# USB_PCB.net
KiCad netlist of a schematic drawn in Altium Designer
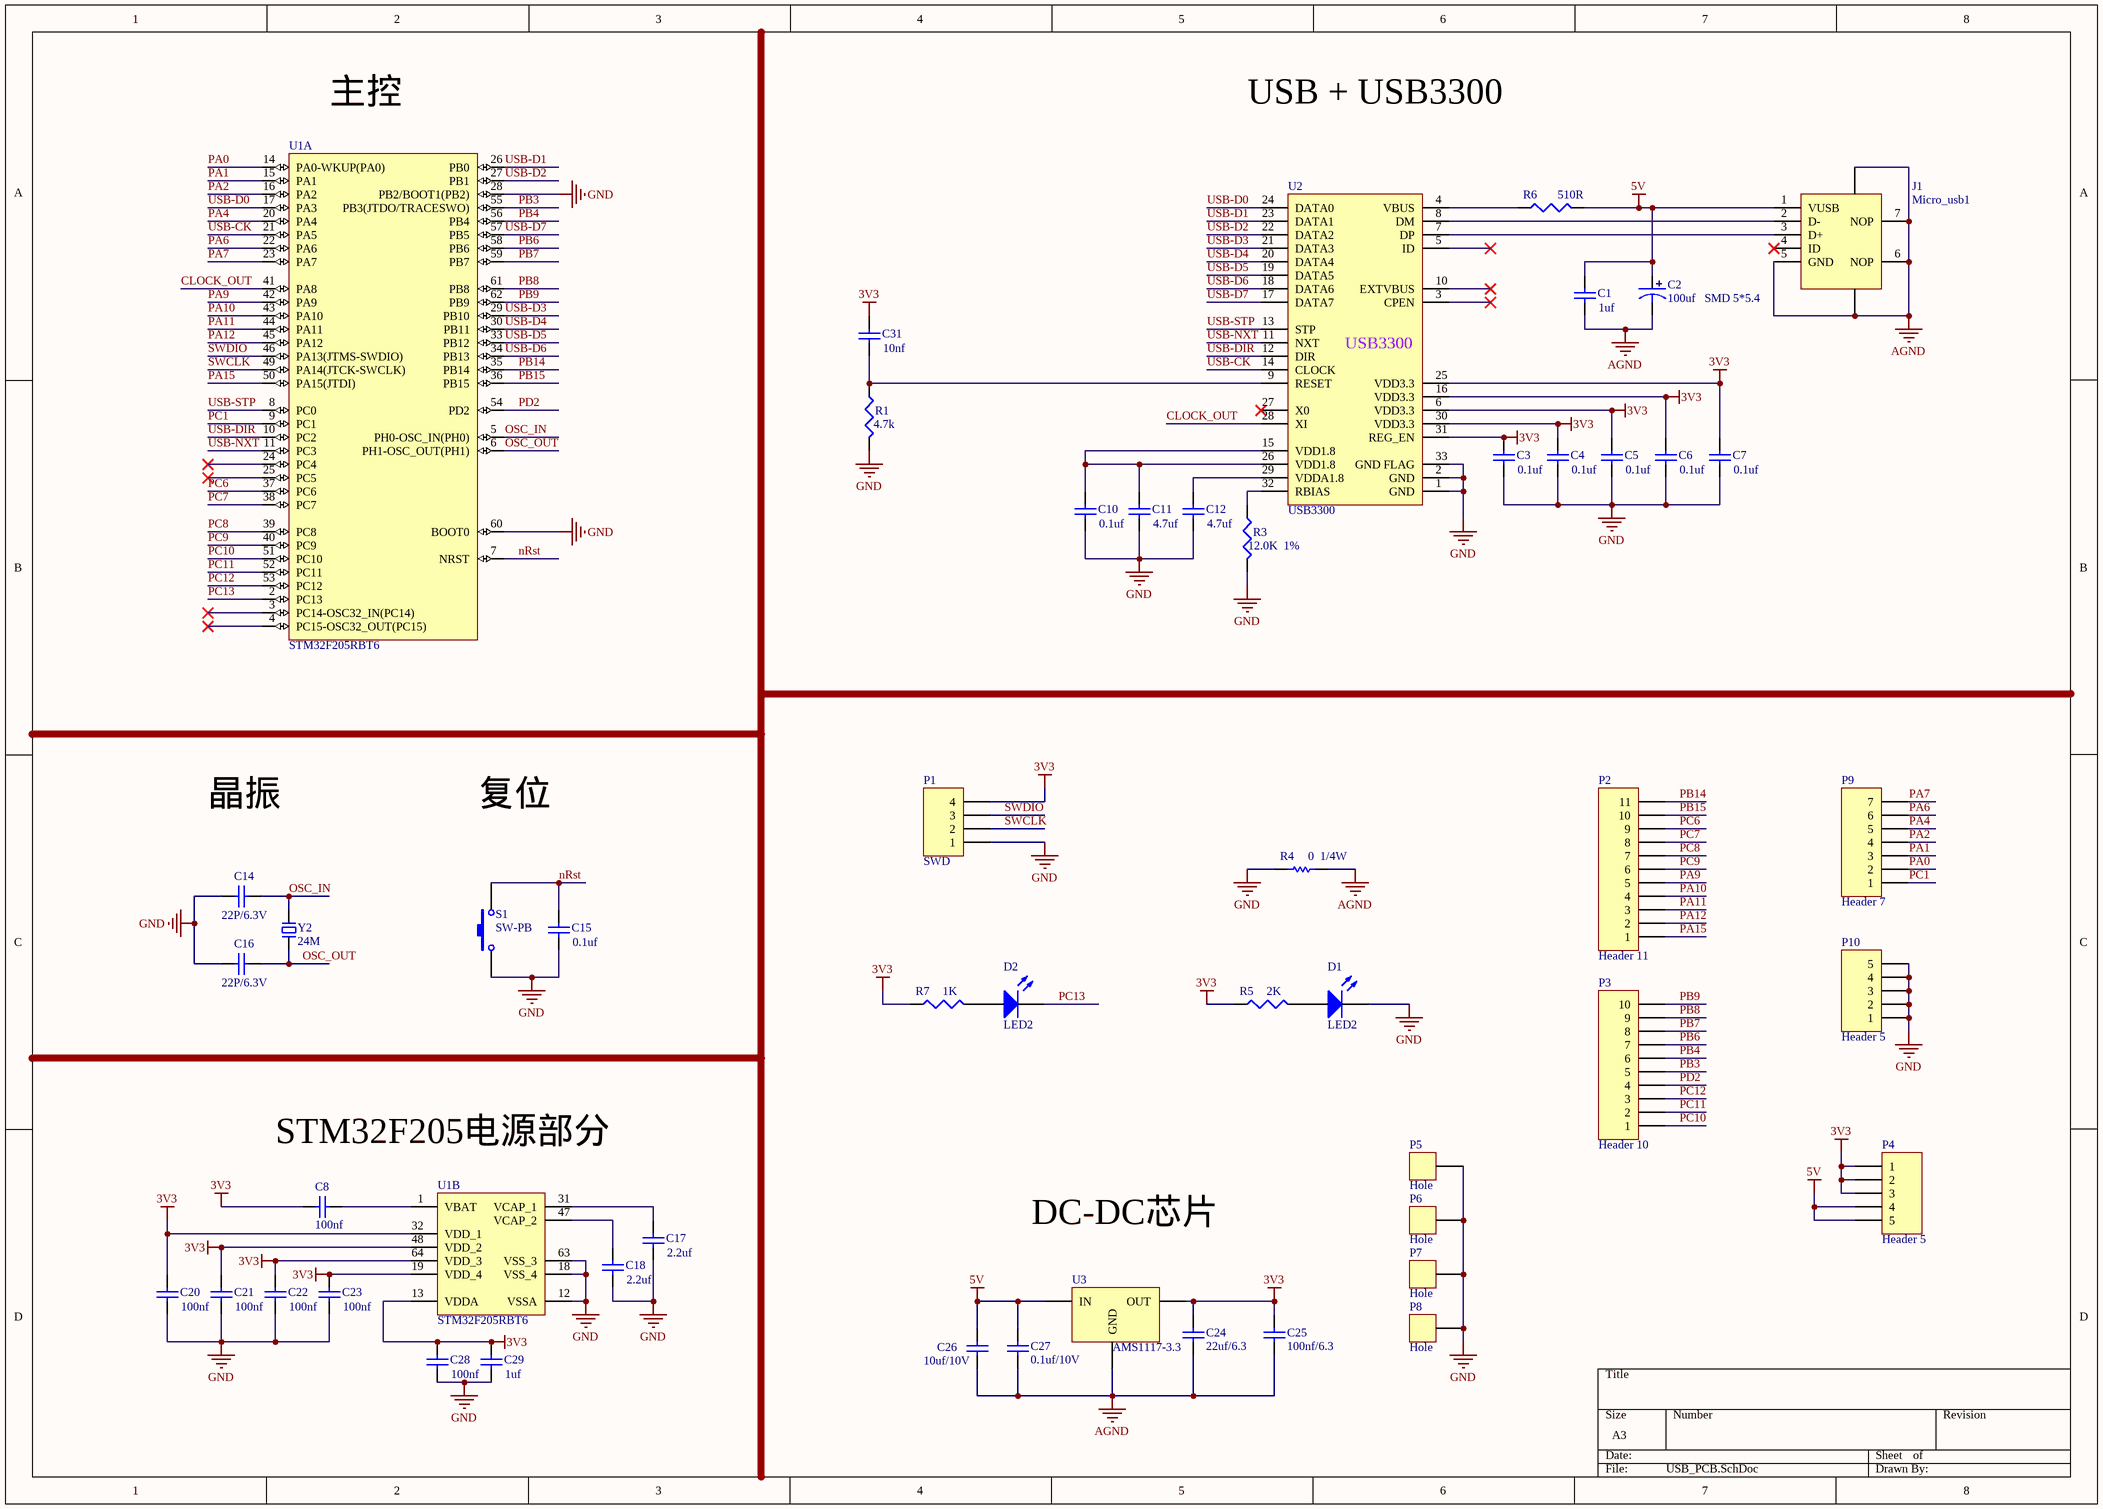
[diagram p0: USB_PCB.SchDoc]

(export (version "E")
  (design (tool "Eeschema 10.0.6"))
  (components
    (comp (ref "C1")
      (value "1uf")
      (footprint "j1-0603")
      (description "Capacitor (Semiconductor SIM Model)")
      (fields (field (name "PUBLISHER") "Altium Limited"))
      (libsource (lib "Miscellaneous Devices") (part "Cap Semi"))
    )
    (comp (ref "C2")
      (value "100uf   SMD 5*5.4")
      (footprint "SMD-EC5.0X5.3X5.4")
      (description "贴片电解电容")
      (libsource (lib "电容") (part "SMD_ECAP"))
    )
    (comp (ref "C3")
      (value "0.1uf")
      (footprint "j1-0603")
      (description "Capacitor (Semiconductor SIM Model)")
      (fields (field (name "PUBLISHER") "Altium Limited"))
      (libsource (lib "Miscellaneous Devices") (part "Cap Semi"))
    )
    (comp (ref "C4")
      (value "0.1uf")
      (footprint "j1-0603")
      (description "Capacitor (Semiconductor SIM Model)")
      (fields (field (name "PUBLISHER") "Altium Limited"))
      (libsource (lib "Miscellaneous Devices") (part "Cap Semi"))
    )
    (comp (ref "C5")
      (value "0.1uf")
      (footprint "j1-0603")
      (description "Capacitor (Semiconductor SIM Model)")
      (fields (field (name "PUBLISHER") "Altium Limited"))
      (libsource (lib "Miscellaneous Devices") (part "Cap Semi"))
    )
    (comp (ref "C6")
      (value "0.1uf")
      (footprint "j1-0603")
      (description "Capacitor (Semiconductor SIM Model)")
      (fields (field (name "PUBLISHER") "Altium Limited"))
      (libsource (lib "Miscellaneous Devices") (part "Cap Semi"))
    )
    (comp (ref "C7")
      (value "0.1uf")
      (footprint "j1-0603")
      (description "Capacitor (Semiconductor SIM Model)")
      (fields (field (name "PUBLISHER") "Altium Limited"))
      (libsource (lib "Miscellaneous Devices") (part "Cap Semi"))
    )
    (comp (ref "C8")
      (value "100nf")
      (footprint "j1-0603")
      (description "Capacitor (Semiconductor SIM Model)")
      (fields (field (name "PUBLISHER") "Altium Limited"))
      (libsource (lib "Miscellaneous Devices") (part "Cap Semi"))
    )
    (comp (ref "C10")
      (value "0.1uf")
      (footprint "j1-0603")
      (description "Capacitor (Semiconductor SIM Model)")
      (fields (field (name "PUBLISHER") "Altium Limited"))
      (libsource (lib "Miscellaneous Devices") (part "Cap Semi"))
    )
    (comp (ref "C11")
      (value "4.7uf")
      (footprint "j1-0603")
      (description "Capacitor (Semiconductor SIM Model)")
      (fields (field (name "PUBLISHER") "Altium Limited"))
      (libsource (lib "Miscellaneous Devices") (part "Cap Semi"))
    )
    (comp (ref "C12")
      (value "4.7uf")
      (footprint "j1-0603")
      (description "Capacitor (Semiconductor SIM Model)")
      (fields (field (name "PUBLISHER") "Altium Limited"))
      (libsource (lib "Miscellaneous Devices") (part "Cap Semi"))
    )
    (comp (ref "C14")
      (value "22P/6.3V")
      (footprint "J1-0603")
      (description "Capacitor")
      (fields (field (name "PUBLISHER") "Altium Limited"))
      (libsource (lib "Miscellaneous Devices") (part "Cap"))
    )
    (comp (ref "C15")
      (value "0.1uf")
      (footprint "j1-0603")
      (description "Capacitor (Semiconductor SIM Model)")
      (fields (field (name "PUBLISHER") "Altium Limited"))
      (libsource (lib "Miscellaneous Devices") (part "Cap Semi"))
    )
    (comp (ref "C16")
      (value "22P/6.3V")
      (footprint "J1-0603")
      (description "Capacitor")
      (fields (field (name "PUBLISHER") "Altium Limited"))
      (libsource (lib "Miscellaneous Devices") (part "Cap"))
    )
    (comp (ref "C17")
      (value "2.2uf")
      (footprint "j1-0603")
      (description "Capacitor (Semiconductor SIM Model)")
      (fields (field (name "PUBLISHER") "Altium Limited"))
      (libsource (lib "Miscellaneous Devices") (part "Cap Semi"))
    )
    (comp (ref "C18")
      (value "2.2uf")
      (footprint "j1-0603")
      (description "Capacitor (Semiconductor SIM Model)")
      (fields (field (name "PUBLISHER") "Altium Limited"))
      (libsource (lib "Miscellaneous Devices") (part "Cap Semi"))
    )
    (comp (ref "C20")
      (value "100nf")
      (footprint "j1-0603")
      (description "Capacitor (Semiconductor SIM Model)")
      (fields (field (name "PUBLISHER") "Altium Limited"))
      (libsource (lib "Miscellaneous Devices") (part "Cap Semi"))
    )
    (comp (ref "C21")
      (value "100nf")
      (footprint "j1-0603")
      (description "Capacitor (Semiconductor SIM Model)")
      (fields (field (name "PUBLISHER") "Altium Limited"))
      (libsource (lib "Miscellaneous Devices") (part "Cap Semi"))
    )
    (comp (ref "C22")
      (value "100nf")
      (footprint "j1-0603")
      (description "Capacitor (Semiconductor SIM Model)")
      (fields (field (name "PUBLISHER") "Altium Limited"))
      (libsource (lib "Miscellaneous Devices") (part "Cap Semi"))
    )
    (comp (ref "C23")
      (value "100nf")
      (footprint "j1-0603")
      (description "Capacitor (Semiconductor SIM Model)")
      (fields (field (name "PUBLISHER") "Altium Limited"))
      (libsource (lib "Miscellaneous Devices") (part "Cap Semi"))
    )
    (comp (ref "C24")
      (value "22uf/6.3")
      (footprint "J1-0603")
      (description "Capacitor")
      (fields (field (name "PUBLISHER") "Altium Limited"))
      (libsource (lib "Miscellaneous Devices") (part "Cap"))
    )
    (comp (ref "C25")
      (value "100nf/6.3")
      (footprint "J1-0603")
      (description "Capacitor")
      (fields (field (name "PUBLISHER") "Altium Limited"))
      (libsource (lib "Miscellaneous Devices") (part "Cap"))
    )
    (comp (ref "C26")
      (value "10uf/10V")
      (footprint "J1-0603")
      (description "Capacitor")
      (fields (field (name "PUBLISHER") "Altium Limited"))
      (libsource (lib "Miscellaneous Devices") (part "Cap"))
    )
    (comp (ref "C27")
      (value "0.1uf/10V")
      (footprint "J1-0603")
      (description "Capacitor")
      (fields (field (name "PUBLISHER") "Altium Limited"))
      (libsource (lib "Miscellaneous Devices") (part "Cap"))
    )
    (comp (ref "C28")
      (value "100nf")
      (footprint "j1-0603")
      (description "Capacitor (Semiconductor SIM Model)")
      (fields (field (name "PUBLISHER") "Altium Limited"))
      (libsource (lib "Miscellaneous Devices") (part "Cap Semi"))
    )
    (comp (ref "C29")
      (value "1uf")
      (footprint "j1-0603")
      (description "Capacitor (Semiconductor SIM Model)")
      (fields (field (name "PUBLISHER") "Altium Limited"))
      (libsource (lib "Miscellaneous Devices") (part "Cap Semi"))
    )
    (comp (ref "C31")
      (value "10nf")
      (footprint "j1-0603")
      (description "Capacitor (Semiconductor SIM Model)")
      (fields (field (name "PUBLISHER") "Altium Limited"))
      (libsource (lib "Miscellaneous Devices") (part "Cap Semi"))
    )
    (comp (ref "D1")
      (value "LED2")
      (footprint "j1-0603")
      (description "Typical RED, GREEN, YELLOW, AMBER GaAs LED")
      (fields (field (name "PUBLISHER") "Altium Limited"))
      (libsource (lib "Miscellaneous Devices") (part "LED2"))
    )
    (comp (ref "D2")
      (value "LED2")
      (footprint "j1-0603")
      (description "Typical RED, GREEN, YELLOW, AMBER GaAs LED")
      (fields (field (name "PUBLISHER") "Altium Limited"))
      (libsource (lib "Miscellaneous Devices") (part "LED2"))
    )
    (comp (ref "J1")
      (value "Micro_usb1")
      (footprint "Micro_USB1")
      (libsource (lib "haoxaingyin") (part "Micro_usb1"))
    )
    (comp (ref "P1")
      (value "SWD")
      (footprint "HDR1X4")
      (description "Header, 4-Pin")
      (fields (field (name "PUBLISHER") "Altium Limited"))
      (libsource (lib "Common Headers") (part "Header 4"))
    )
    (comp (ref "P2")
      (value "Header 11")
      (footprint "HDR1X11")
      (description "Header, 11-Pin")
      (fields (field (name "PUBLISHER") "Altium Limited"))
      (libsource (lib "Common Headers") (part "Header 11"))
    )
    (comp (ref "P3")
      (value "Header 10")
      (footprint "HDR1X10")
      (description "Header, 10-Pin")
      (fields (field (name "PUBLISHER") "Altium Limited"))
      (libsource (lib "Common Headers") (part "Header 10"))
    )
    (comp (ref "P4")
      (value "Header 5")
      (footprint "HDR1X5")
      (description "Header, 5-Pin")
      (fields (field (name "PUBLISHER") "Altium Limited"))
      (libsource (lib "") (part "Header 5_1"))
    )
    (comp (ref "P5") (value "Hole") (footprint "Hole") (libsource (lib "haoxaingyin") (part "Hole")))
    (comp (ref "P6") (value "Hole") (footprint "Hole") (libsource (lib "haoxaingyin") (part "Hole")))
    (comp (ref "P7") (value "Hole") (footprint "Hole") (libsource (lib "haoxaingyin") (part "Hole")))
    (comp (ref "P8") (value "Hole") (footprint "Hole") (libsource (lib "haoxaingyin") (part "Hole")))
    (comp (ref "P9")
      (value "Header 7")
      (footprint "HDR1X7")
      (description "Header, 7-Pin")
      (fields (field (name "PUBLISHER") "Altium Limited"))
      (libsource (lib "Common Headers") (part "Header 7"))
    )
    (comp (ref "P10")
      (value "Header 5")
      (footprint "HDR1X5")
      (description "Header, 5-Pin")
      (fields (field (name "PUBLISHER") "Altium Limited"))
      (libsource (lib "Common Headers") (part "Header 5"))
    )
    (comp (ref "R1")
      (value "4.7k")
      (footprint "J1-0603")
      (description "Resistor")
      (fields (field (name "PUBLISHER") "Altium Limited"))
      (libsource (lib "Miscellaneous Devices") (part "Res3"))
    )
    (comp (ref "R3")
      (value "12.0K  1%")
      (footprint "J1-0603")
      (description "Resistor")
      (fields (field (name "PUBLISHER") "Altium Limited"))
      (libsource (lib "Miscellaneous Devices") (part "Res3"))
    )
    (comp (ref "R4") (value "0  1/4W") (footprint "AXIAL0.4") (libsource (lib "电阻") (part "RES")))
    (comp (ref "R5")
      (value "2K")
      (footprint "J1-0603")
      (description "Resistor")
      (fields (field (name "PUBLISHER") "Altium Limited"))
      (libsource (lib "Miscellaneous Devices") (part "Res3"))
    )
    (comp (ref "R6")
      (value "510R")
      (footprint "J1-0603")
      (description "Resistor")
      (fields (field (name "PUBLISHER") "Altium Limited"))
      (libsource (lib "Miscellaneous Devices") (part "Res3"))
    )
    (comp (ref "R7")
      (value "1K")
      (footprint "J1-0603")
      (description "Resistor")
      (fields (field (name "PUBLISHER") "Altium Limited"))
      (libsource (lib "Miscellaneous Devices") (part "Res3"))
    )
    (comp (ref "S1")
      (value "SW-PB")
      (footprint "TD-19XA")
      (description "Switch")
      (fields (field (name "PUBLISHER") "Altium Limited"))
      (libsource (lib "Miscellaneous Devices") (part "SW-PB"))
    )
    (comp (ref "U1")
      (value "STM32F205RBT6")
      (footprint "STM-LQFP64_N")
      (libsource (lib "STMicroelectronics STM32 F2") (part "STM32F205RBT6"))
    )
    (comp (ref "U2") (value "USB3300") (footprint "QFN32_L") (libsource (lib "haoxaingyin") (part "USB3300")))
    (comp (ref "U3")
      (value "AMS1117-3.3")
      (footprint "SOT-223")
      (libsource (lib "Common Power") (part "ASM1117"))
    )
    (comp (ref "Y2")
      (value "24M")
      (footprint "OSC 5032-2P")
      (description "2脚无源脚晶振")
      (libsource (lib "晶振") (part "XTAL-2P"))
    )
  )
  (nets
    (net (code "1") (name "/CLOCK_OUT") (class "Default")
      (node (ref "U1") (pin "41") (pinfunction "PA8_41") (pintype "bidirectional"))
      (node (ref "U2") (pin "28") (pinfunction "XI_28") (pintype "passive"))
    )
    (net (code "2") (name "/OSC_IN") (class "Default")
      (node (ref "C14") (pin "2") (pinfunction "2_2") (pintype "passive"))
      (node (ref "U1") (pin "5") (pinfunction "PH0-OSC_IN(PH0)_5") (pintype "bidirectional"))
      (node (ref "Y2") (pin "2") (pinfunction "2_2") (pintype "passive"))
    )
    (net (code "3") (name "/OSC_OUT") (class "Default")
      (node (ref "C16") (pin "2") (pinfunction "2_2") (pintype "passive"))
      (node (ref "U1") (pin "6") (pinfunction "PH1-OSC_OUT(PH1)_6") (pintype "bidirectional"))
      (node (ref "Y2") (pin "1") (pinfunction "1_1") (pintype "passive"))
    )
    (net (code "4") (name "/PA0") (class "Default")
      (node (ref "P9") (pin "2") (pinfunction "2_2") (pintype "passive"))
      (node (ref "U1") (pin "14") (pinfunction "PA0-WKUP(PA0)_14") (pintype "bidirectional"))
    )
    (net (code "5") (name "/PA1") (class "Default")
      (node (ref "P9") (pin "3") (pinfunction "3_3") (pintype "passive"))
      (node (ref "U1") (pin "15") (pinfunction "PA1_15") (pintype "bidirectional"))
    )
    (net (code "6") (name "/PA2") (class "Default")
      (node (ref "P9") (pin "4") (pinfunction "4_4") (pintype "passive"))
      (node (ref "U1") (pin "16") (pinfunction "PA2_16") (pintype "bidirectional"))
    )
    (net (code "7") (name "/PA4") (class "Default")
      (node (ref "P9") (pin "5") (pinfunction "5_5") (pintype "passive"))
      (node (ref "U1") (pin "20") (pinfunction "PA4_20") (pintype "bidirectional"))
    )
    (net (code "8") (name "/PA6") (class "Default")
      (node (ref "P9") (pin "6") (pinfunction "6_6") (pintype "passive"))
      (node (ref "U1") (pin "22") (pinfunction "PA6_22") (pintype "bidirectional"))
    )
    (net (code "9") (name "/PA7") (class "Default")
      (node (ref "P9") (pin "7") (pinfunction "7_7") (pintype "passive"))
      (node (ref "U1") (pin "23") (pinfunction "PA7_23") (pintype "bidirectional"))
    )
    (net (code "10") (name "/PA9") (class "Default")
      (node (ref "P2") (pin "5") (pinfunction "5_5") (pintype "passive"))
      (node (ref "U1") (pin "42") (pinfunction "PA9_42") (pintype "bidirectional"))
    )
    (net (code "11") (name "/PA10") (class "Default")
      (node (ref "P2") (pin "4") (pinfunction "4_4") (pintype "passive"))
      (node (ref "U1") (pin "43") (pinfunction "PA10_43") (pintype "bidirectional"))
    )
    (net (code "12") (name "/PA11") (class "Default")
      (node (ref "P2") (pin "3") (pinfunction "3_3") (pintype "passive"))
      (node (ref "U1") (pin "44") (pinfunction "PA11_44") (pintype "bidirectional"))
    )
    (net (code "13") (name "/PA12") (class "Default")
      (node (ref "P2") (pin "2") (pinfunction "2_2") (pintype "passive"))
      (node (ref "U1") (pin "45") (pinfunction "PA12_45") (pintype "bidirectional"))
    )
    (net (code "14") (name "/PA15") (class "Default")
      (node (ref "P2") (pin "1") (pinfunction "1_1") (pintype "passive"))
      (node (ref "U1") (pin "50") (pinfunction "PA15(JTDI)_50") (pintype "bidirectional"))
    )
    (net (code "15") (name "/PB3") (class "Default")
      (node (ref "P3") (pin "5") (pinfunction "5_5") (pintype "passive"))
      (node (ref "U1") (pin "55") (pinfunction "PB3(JTDO/TRACESWO)_55") (pintype "bidirectional"))
    )
    (net (code "16") (name "/PB4") (class "Default")
      (node (ref "P3") (pin "6") (pinfunction "6_6") (pintype "passive"))
      (node (ref "U1") (pin "56") (pinfunction "PB4_56") (pintype "bidirectional"))
    )
    (net (code "17") (name "/PB6") (class "Default")
      (node (ref "P3") (pin "7") (pinfunction "7_7") (pintype "passive"))
      (node (ref "U1") (pin "58") (pinfunction "PB6_58") (pintype "bidirectional"))
    )
    (net (code "18") (name "/PB7") (class "Default")
      (node (ref "P3") (pin "8") (pinfunction "8_8") (pintype "passive"))
      (node (ref "U1") (pin "59") (pinfunction "PB7_59") (pintype "bidirectional"))
    )
    (net (code "19") (name "/PB8") (class "Default")
      (node (ref "P3") (pin "9") (pinfunction "9_9") (pintype "passive"))
      (node (ref "U1") (pin "61") (pinfunction "PB8_61") (pintype "bidirectional"))
    )
    (net (code "20") (name "/PB9") (class "Default")
      (node (ref "P3") (pin "10") (pinfunction "10_10") (pintype "passive"))
      (node (ref "U1") (pin "62") (pinfunction "PB9_62") (pintype "bidirectional"))
    )
    (net (code "21") (name "/PB14") (class "Default")
      (node (ref "P2") (pin "11") (pinfunction "11_11") (pintype "passive"))
      (node (ref "U1") (pin "35") (pinfunction "PB14_35") (pintype "bidirectional"))
    )
    (net (code "22") (name "/PB15") (class "Default")
      (node (ref "P2") (pin "10") (pinfunction "10_10") (pintype "passive"))
      (node (ref "U1") (pin "36") (pinfunction "PB15_36") (pintype "bidirectional"))
    )
    (net (code "23") (name "/PC1") (class "Default")
      (node (ref "P9") (pin "1") (pinfunction "1_1") (pintype "passive"))
      (node (ref "U1") (pin "9") (pinfunction "PC1_9") (pintype "bidirectional"))
    )
    (net (code "24") (name "/PC6") (class "Default")
      (node (ref "P2") (pin "9") (pinfunction "9_9") (pintype "passive"))
      (node (ref "U1") (pin "37") (pinfunction "PC6_37") (pintype "bidirectional"))
    )
    (net (code "25") (name "/PC7") (class "Default")
      (node (ref "P2") (pin "8") (pinfunction "8_8") (pintype "passive"))
      (node (ref "U1") (pin "38") (pinfunction "PC7_38") (pintype "bidirectional"))
    )
    (net (code "26") (name "/PC8") (class "Default")
      (node (ref "P2") (pin "7") (pinfunction "7_7") (pintype "passive"))
      (node (ref "U1") (pin "39") (pinfunction "PC8_39") (pintype "bidirectional"))
    )
    (net (code "27") (name "/PC9") (class "Default")
      (node (ref "P2") (pin "6") (pinfunction "6_6") (pintype "passive"))
      (node (ref "U1") (pin "40") (pinfunction "PC9_40") (pintype "bidirectional"))
    )
    (net (code "28") (name "/PC10") (class "Default")
      (node (ref "P3") (pin "1") (pinfunction "1_1") (pintype "passive"))
      (node (ref "U1") (pin "51") (pinfunction "PC10_51") (pintype "bidirectional"))
    )
    (net (code "29") (name "/PC11") (class "Default")
      (node (ref "P3") (pin "2") (pinfunction "2_2") (pintype "passive"))
      (node (ref "U1") (pin "52") (pinfunction "PC11_52") (pintype "bidirectional"))
    )
    (net (code "30") (name "/PC12") (class "Default")
      (node (ref "P3") (pin "3") (pinfunction "3_3") (pintype "passive"))
      (node (ref "U1") (pin "53") (pinfunction "PC12_53") (pintype "bidirectional"))
    )
    (net (code "31") (name "/PC13") (class "Default")
      (node (ref "D2") (pin "2") (pinfunction "K_2") (pintype "passive"))
      (node (ref "U1") (pin "2") (pinfunction "PC13_2") (pintype "bidirectional"))
    )
    (net (code "32") (name "/PD2") (class "Default")
      (node (ref "P3") (pin "4") (pinfunction "4_4") (pintype "passive"))
      (node (ref "U1") (pin "54") (pinfunction "PD2_54") (pintype "bidirectional"))
    )
    (net (code "33") (name "/SWCLK") (class "Default")
      (node (ref "P1") (pin "2") (pinfunction "2_2") (pintype "passive"))
      (node (ref "U1") (pin "49") (pinfunction "PA14(JTCK-SWCLK)_49") (pintype "bidirectional"))
    )
    (net (code "34") (name "/SWDIO") (class "Default")
      (node (ref "P1") (pin "3") (pinfunction "3_3") (pintype "passive"))
      (node (ref "U1") (pin "46") (pinfunction "PA13(JTMS-SWDIO)_46") (pintype "bidirectional"))
    )
    (net (code "35") (name "/USB-CK") (class "Default")
      (node (ref "U1") (pin "21") (pinfunction "PA5_21") (pintype "bidirectional"))
      (node (ref "U2") (pin "14") (pinfunction "CLOCK_14") (pintype "passive"))
    )
    (net (code "36") (name "/USB-D0") (class "Default")
      (node (ref "U1") (pin "17") (pinfunction "PA3_17") (pintype "bidirectional"))
      (node (ref "U2") (pin "24") (pinfunction "DATA0_24") (pintype "passive"))
    )
    (net (code "37") (name "/USB-D1") (class "Default")
      (node (ref "U1") (pin "26") (pinfunction "PB0_26") (pintype "bidirectional"))
      (node (ref "U2") (pin "23") (pinfunction "DATA1_23") (pintype "passive"))
    )
    (net (code "38") (name "/USB-D2") (class "Default")
      (node (ref "U1") (pin "27") (pinfunction "PB1_27") (pintype "bidirectional"))
      (node (ref "U2") (pin "22") (pinfunction "DATA2_22") (pintype "passive"))
    )
    (net (code "39") (name "/USB-D3") (class "Default")
      (node (ref "U1") (pin "29") (pinfunction "PB10_29") (pintype "bidirectional"))
      (node (ref "U2") (pin "21") (pinfunction "DATA3_21") (pintype "passive"))
    )
    (net (code "40") (name "/USB-D4") (class "Default")
      (node (ref "U1") (pin "30") (pinfunction "PB11_30") (pintype "bidirectional"))
      (node (ref "U2") (pin "20") (pinfunction "DATA4_20") (pintype "passive"))
    )
    (net (code "41") (name "/USB-D5") (class "Default")
      (node (ref "U1") (pin "33") (pinfunction "PB12_33") (pintype "bidirectional"))
      (node (ref "U2") (pin "19") (pinfunction "DATA5_19") (pintype "passive"))
    )
    (net (code "42") (name "/USB-D6") (class "Default")
      (node (ref "U1") (pin "34") (pinfunction "PB13_34") (pintype "bidirectional"))
      (node (ref "U2") (pin "18") (pinfunction "DATA6_18") (pintype "passive"))
    )
    (net (code "43") (name "/USB-D7") (class "Default")
      (node (ref "U1") (pin "57") (pinfunction "PB5_57") (pintype "bidirectional"))
      (node (ref "U2") (pin "17") (pinfunction "DATA7_17") (pintype "passive"))
    )
    (net (code "44") (name "/USB-DIR") (class "Default")
      (node (ref "U1") (pin "10") (pinfunction "PC2_10") (pintype "bidirectional"))
      (node (ref "U2") (pin "12") (pinfunction "DIR_12") (pintype "passive"))
    )
    (net (code "45") (name "/USB-NXT") (class "Default")
      (node (ref "U1") (pin "11") (pinfunction "PC3_11") (pintype "bidirectional"))
      (node (ref "U2") (pin "11") (pinfunction "NXT_11") (pintype "passive"))
    )
    (net (code "46") (name "/USB-STP") (class "Default")
      (node (ref "U1") (pin "8") (pinfunction "PC0_8") (pintype "bidirectional"))
      (node (ref "U2") (pin "13") (pinfunction "STP_13") (pintype "passive"))
    )
    (net (code "47") (name "/nRst") (class "Default")
      (node (ref "C15") (pin "2") (pinfunction "2_2") (pintype "passive"))
      (node (ref "S1") (pin "2") (pinfunction "2_2") (pintype "passive"))
      (node (ref "U1") (pin "7") (pinfunction "NRST_7") (pintype "bidirectional"))
    )
    (net (code "48") (name "3V3") (class "Default")
      (node (ref "C20") (pin "2") (pinfunction "2_2") (pintype "passive"))
      (node (ref "C21") (pin "2") (pinfunction "2_2") (pintype "passive"))
      (node (ref "C22") (pin "2") (pinfunction "2_2") (pintype "passive"))
      (node (ref "C23") (pin "2") (pinfunction "2_2") (pintype "passive"))
      (node (ref "C24") (pin "2") (pinfunction "2_2") (pintype "passive"))
      (node (ref "C25") (pin "2") (pinfunction "2_2") (pintype "passive"))
      (node (ref "C28") (pin "2") (pinfunction "2_2") (pintype "passive"))
      (node (ref "C29") (pin "2") (pinfunction "2_2") (pintype "passive"))
      (node (ref "C3") (pin "2") (pinfunction "2_2") (pintype "passive"))
      (node (ref "C31") (pin "2") (pinfunction "2_2") (pintype "passive"))
      (node (ref "C4") (pin "2") (pinfunction "2_2") (pintype "passive"))
      (node (ref "C5") (pin "2") (pinfunction "2_2") (pintype "passive"))
      (node (ref "C6") (pin "2") (pinfunction "2_2") (pintype "passive"))
      (node (ref "C7") (pin "2") (pinfunction "2_2") (pintype "passive"))
      (node (ref "C8") (pin "2") (pinfunction "2_2") (pintype "passive"))
      (node (ref "P1") (pin "4") (pinfunction "4_4") (pintype "passive"))
      (node (ref "P4") (pin "1") (pinfunction "1_1") (pintype "passive"))
      (node (ref "P4") (pin "2") (pinfunction "2_2") (pintype "passive"))
      (node (ref "P4") (pin "3") (pinfunction "3_3") (pintype "passive"))
      (node (ref "R5") (pin "1") (pinfunction "1_1") (pintype "passive"))
      (node (ref "R7") (pin "1") (pinfunction "1_1") (pintype "passive"))
      (node (ref "U1") (pin "13") (pinfunction "VDDA_13") (pintype "power_in"))
      (node (ref "U1") (pin "19") (pinfunction "VDD_4_19") (pintype "power_in"))
      (node (ref "U1") (pin "32") (pinfunction "VDD_1_32") (pintype "power_in"))
      (node (ref "U1") (pin "48") (pinfunction "VDD_2_48") (pintype "power_in"))
      (node (ref "U1") (pin "64") (pinfunction "VDD_3_64") (pintype "power_in"))
      (node (ref "U2") (pin "16") (pinfunction "VDD3.3_16") (pintype "passive"))
      (node (ref "U2") (pin "25") (pinfunction "VDD3.3_25") (pintype "passive"))
      (node (ref "U2") (pin "30") (pinfunction "VDD3.3_30") (pintype "passive"))
      (node (ref "U2") (pin "31") (pinfunction "REG_EN_31") (pintype "passive"))
      (node (ref "U2") (pin "6") (pinfunction "VDD3.3_6") (pintype "passive"))
      (node (ref "U3") (pin "2") (pinfunction "OUT_2") (pintype "passive"))
    )
    (net (code "49") (name "5V") (class "Default")
      (node (ref "C1") (pin "2") (pinfunction "2_2") (pintype "passive"))
      (node (ref "C2") (pin "1") (pinfunction "1_1") (pintype "passive"))
      (node (ref "C26") (pin "2") (pinfunction "2_2") (pintype "passive"))
      (node (ref "C27") (pin "2") (pinfunction "2_2") (pintype "passive"))
      (node (ref "J1") (pin "1") (pinfunction "VUSB_1") (pintype "passive"))
      (node (ref "P4") (pin "4") (pinfunction "4_4") (pintype "passive"))
      (node (ref "P4") (pin "5") (pinfunction "5_5") (pintype "passive"))
      (node (ref "R6") (pin "2") (pinfunction "2_2") (pintype "passive"))
      (node (ref "U3") (pin "3") (pinfunction "IN_3") (pintype "passive"))
    )
    (net (code "50") (name "AGND") (class "Default")
      (node (ref "C1") (pin "1") (pinfunction "1_1") (pintype "passive"))
      (node (ref "C2") (pin "2") (pinfunction "2_2") (pintype "passive"))
      (node (ref "C24") (pin "1") (pinfunction "1_1") (pintype "passive"))
      (node (ref "C25") (pin "1") (pinfunction "1_1") (pintype "passive"))
      (node (ref "C26") (pin "1") (pinfunction "1_1") (pintype "passive"))
      (node (ref "C27") (pin "1") (pinfunction "1_1") (pintype "passive"))
      (node (ref "J1") (pin "5") (pinfunction "GND_5") (pintype "passive"))
      (node (ref "J1") (pin "6") (pinfunction "NOP_6") (pintype "passive"))
      (node (ref "J1") (pin "7") (pinfunction "NOP_7") (pintype "passive"))
      (node (ref "J1") (pin "8") (pinfunction "8_8") (pintype "passive"))
      (node (ref "J1") (pin "9") (pinfunction "9_9") (pintype "passive"))
      (node (ref "R4") (pin "2") (pinfunction "2_2") (pintype "passive"))
      (node (ref "U3") (pin "1") (pinfunction "GND_1") (pintype "passive"))
    )
    (net (code "51") (name "GND") (class "Default")
      (node (ref "C10") (pin "1") (pinfunction "1_1") (pintype "passive"))
      (node (ref "C11") (pin "1") (pinfunction "1_1") (pintype "passive"))
      (node (ref "C12") (pin "1") (pinfunction "1_1") (pintype "passive"))
      (node (ref "C14") (pin "1") (pinfunction "1_1") (pintype "passive"))
      (node (ref "C15") (pin "1") (pinfunction "1_1") (pintype "passive"))
      (node (ref "C16") (pin "1") (pinfunction "1_1") (pintype "passive"))
      (node (ref "C17") (pin "1") (pinfunction "1_1") (pintype "passive"))
      (node (ref "C18") (pin "1") (pinfunction "1_1") (pintype "passive"))
      (node (ref "C20") (pin "1") (pinfunction "1_1") (pintype "passive"))
      (node (ref "C21") (pin "1") (pinfunction "1_1") (pintype "passive"))
      (node (ref "C22") (pin "1") (pinfunction "1_1") (pintype "passive"))
      (node (ref "C23") (pin "1") (pinfunction "1_1") (pintype "passive"))
      (node (ref "C28") (pin "1") (pinfunction "1_1") (pintype "passive"))
      (node (ref "C29") (pin "1") (pinfunction "1_1") (pintype "passive"))
      (node (ref "C3") (pin "1") (pinfunction "1_1") (pintype "passive"))
      (node (ref "C4") (pin "1") (pinfunction "1_1") (pintype "passive"))
      (node (ref "C5") (pin "1") (pinfunction "1_1") (pintype "passive"))
      (node (ref "C6") (pin "1") (pinfunction "1_1") (pintype "passive"))
      (node (ref "C7") (pin "1") (pinfunction "1_1") (pintype "passive"))
      (node (ref "D1") (pin "2") (pinfunction "K_2") (pintype "passive"))
      (node (ref "P1") (pin "1") (pinfunction "1_1") (pintype "passive"))
      (node (ref "P10") (pin "1") (pinfunction "1_1") (pintype "passive"))
      (node (ref "P10") (pin "2") (pinfunction "2_2") (pintype "passive"))
      (node (ref "P10") (pin "3") (pinfunction "3_3") (pintype "passive"))
      (node (ref "P10") (pin "4") (pinfunction "4_4") (pintype "passive"))
      (node (ref "P10") (pin "5") (pinfunction "5_5") (pintype "passive"))
      (node (ref "P5") (pin "1") (pinfunction "1_1") (pintype "passive"))
      (node (ref "P6") (pin "1") (pinfunction "1_1") (pintype "passive"))
      (node (ref "P7") (pin "1") (pinfunction "1_1") (pintype "passive"))
      (node (ref "P8") (pin "1") (pinfunction "1_1") (pintype "passive"))
      (node (ref "R1") (pin "2") (pinfunction "2_2") (pintype "passive"))
      (node (ref "R3") (pin "2") (pinfunction "2_2") (pintype "passive"))
      (node (ref "R4") (pin "1") (pinfunction "1_1") (pintype "passive"))
      (node (ref "S1") (pin "1") (pinfunction "1_1") (pintype "passive"))
      (node (ref "U1") (pin "12") (pinfunction "VSSA_12") (pintype "power_in"))
      (node (ref "U1") (pin "18") (pinfunction "VSS_4_18") (pintype "power_in"))
      (node (ref "U1") (pin "28") (pinfunction "PB2/BOOT1(PB2)_28") (pintype "bidirectional"))
      (node (ref "U1") (pin "60") (pinfunction "BOOT0_60") (pintype "bidirectional"))
      (node (ref "U1") (pin "63") (pinfunction "VSS_3_63") (pintype "power_in"))
      (node (ref "U2") (pin "1") (pinfunction "GND_1") (pintype "passive"))
      (node (ref "U2") (pin "2") (pinfunction "GND_2") (pintype "passive"))
      (node (ref "U2") (pin "33") (pinfunction "GND_FLAG_33") (pintype "passive"))
    )
    (net (code "52") (name "Net-(C10-Pad2)") (class "Default")
      (node (ref "C10") (pin "2") (pinfunction "2_2") (pintype "passive"))
      (node (ref "C11") (pin "2") (pinfunction "2_2") (pintype "passive"))
      (node (ref "U2") (pin "15") (pinfunction "VDD1.8_15") (pintype "passive"))
      (node (ref "U2") (pin "26") (pinfunction "VDD1.8_26") (pintype "passive"))
    )
    (net (code "53") (name "Net-(D1-A)") (class "Default")
      (node (ref "D1") (pin "1") (pinfunction "A_1") (pintype "passive"))
      (node (ref "R5") (pin "2") (pinfunction "2_2") (pintype "passive"))
    )
    (net (code "54") (name "Net-(D2-A)") (class "Default")
      (node (ref "D2") (pin "1") (pinfunction "A_1") (pintype "passive"))
      (node (ref "R7") (pin "2") (pinfunction "2_2") (pintype "passive"))
    )
    (net (code "55") (name "Net-(J1-D+)") (class "Default")
      (node (ref "J1") (pin "3") (pinfunction "D+_3") (pintype "passive"))
      (node (ref "U2") (pin "7") (pinfunction "DP_7") (pintype "passive"))
    )
    (net (code "56") (name "Net-(J1-D-)") (class "Default")
      (node (ref "J1") (pin "2") (pinfunction "D-_2") (pintype "passive"))
      (node (ref "U2") (pin "8") (pinfunction "DM_8") (pintype "passive"))
    )
    (net (code "57") (name "Net-(U1B-VBAT)") (class "Default")
      (node (ref "C8") (pin "1") (pinfunction "1_1") (pintype "passive"))
      (node (ref "U1") (pin "1") (pinfunction "VBAT_1") (pintype "power_in"))
    )
    (net (code "58") (name "Net-(U1B-VCAP_1)") (class "Default")
      (node (ref "C17") (pin "2") (pinfunction "2_2") (pintype "passive"))
      (node (ref "U1") (pin "31") (pinfunction "VCAP_1_31") (pintype "power_in"))
    )
    (net (code "59") (name "Net-(U1B-VCAP_2)") (class "Default")
      (node (ref "C18") (pin "2") (pinfunction "2_2") (pintype "passive"))
      (node (ref "U1") (pin "47") (pinfunction "VCAP_2_47") (pintype "power_in"))
    )
    (net (code "60") (name "Net-(U2-RBIAS)") (class "Default")
      (node (ref "R3") (pin "1") (pinfunction "1_1") (pintype "passive"))
      (node (ref "U2") (pin "32") (pinfunction "RBIAS_32") (pintype "passive"))
    )
    (net (code "61") (name "Net-(U2-RESET)") (class "Default")
      (node (ref "C31") (pin "1") (pinfunction "1_1") (pintype "passive"))
      (node (ref "R1") (pin "1") (pinfunction "1_1") (pintype "passive"))
      (node (ref "U2") (pin "9") (pinfunction "RESET_9") (pintype "passive"))
    )
    (net (code "62") (name "Net-(U2-VBUS)") (class "Default")
      (node (ref "R6") (pin "1") (pinfunction "1_1") (pintype "passive"))
      (node (ref "U2") (pin "4") (pinfunction "VBUS_4") (pintype "passive"))
    )
    (net (code "63") (name "Net-(U2-VDDA1.8)") (class "Default")
      (node (ref "C12") (pin "2") (pinfunction "2_2") (pintype "passive"))
      (node (ref "U2") (pin "29") (pinfunction "VDDA1.8_29") (pintype "passive"))
    )
    (net (code "64") (name "unconnected-(J1-ID-Pad4)") (class "Default")
      (node (ref "J1") (pin "4") (pinfunction "ID_4") (pintype "passive+no_connect"))
    )
    (net (code "65") (name "unconnected-(U1A-PC4-Pad24)") (class "Default")
      (node (ref "U1") (pin "24") (pinfunction "PC4_24") (pintype "bidirectional+no_connect"))
    )
    (net (code "66") (name "unconnected-(U1A-PC5-Pad25)") (class "Default")
      (node (ref "U1") (pin "25") (pinfunction "PC5_25") (pintype "bidirectional+no_connect"))
    )
    (net (code "67") (name "unconnected-(U1A-PC14-OSC32_IN(PC14)-Pad3)") (class "Default")
      (node (ref "U1") (pin "3") (pinfunction "PC14-OSC32_IN(PC14)_3") (pintype "bidirectional+no_connect"))
    )
    (net (code "68") (name "unconnected-(U1A-PC15-OSC32_OUT(PC15)-Pad4)") (class "Default")
      (node (ref "U1") (pin "4") (pinfunction "PC15-OSC32_OUT(PC15)_4") (pintype "bidirectional+no_connect"))
    )
    (net (code "69") (name "unconnected-(U2-CPEN-Pad3)") (class "Default")
      (node (ref "U2") (pin "3") (pinfunction "CPEN_3") (pintype "passive+no_connect"))
    )
    (net (code "70") (name "unconnected-(U2-EXTVBUS-Pad10)") (class "Default")
      (node (ref "U2") (pin "10") (pinfunction "EXTVBUS_10") (pintype "passive+no_connect"))
    )
    (net (code "71") (name "unconnected-(U2-ID-Pad5)") (class "Default")
      (node (ref "U2") (pin "5") (pinfunction "ID_5") (pintype "passive+no_connect"))
    )
    (net (code "72") (name "unconnected-(U2-X0-Pad27)") (class "Default")
      (node (ref "U2") (pin "27") (pinfunction "X0_27") (pintype "passive+no_connect"))
    )
  )
)
